# SCH.net
KiCad netlist of a schematic drawn in EasyEDA Pro
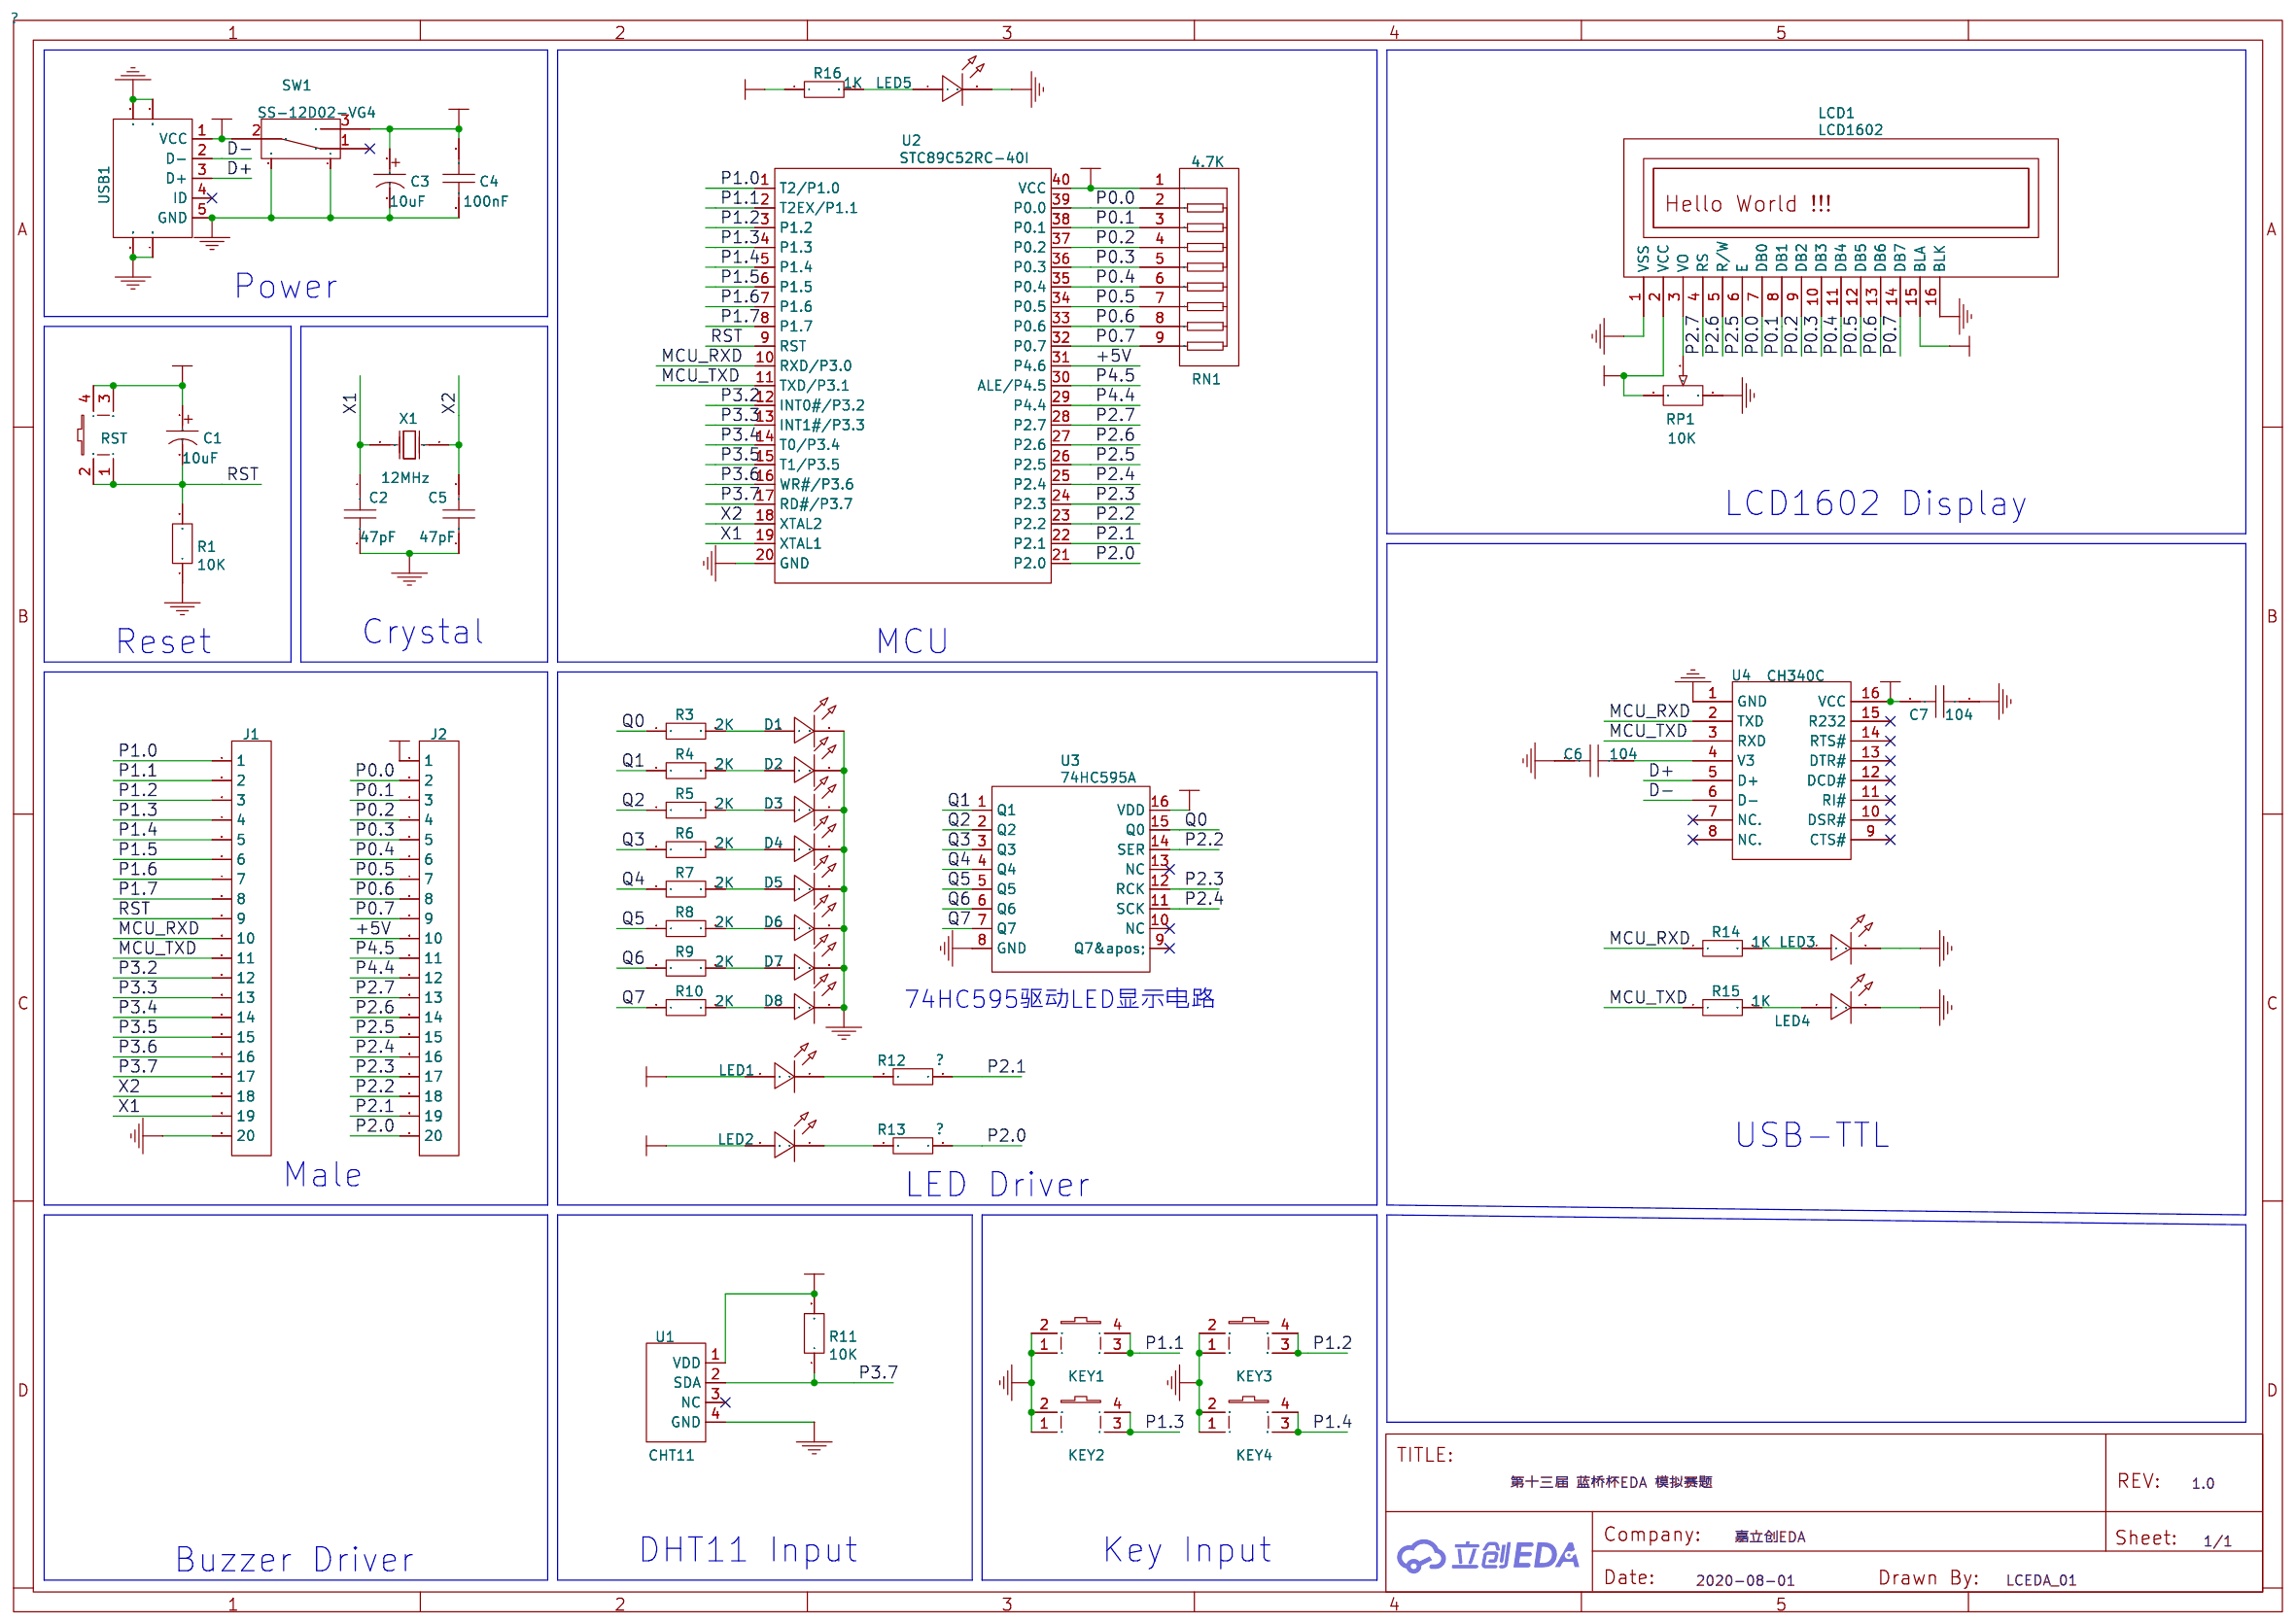
[diagram p0: schematic sheet]

(export (version "E")
  (design (tool "Eeschema 10.0.6"))
  (components
    (comp (ref "C1")
      (value "10uF")
      (fields (field (name "Manufacturer Part") "10uF 25V 5*11") (field (name "Manufacturer") "ValuePro"))
      (libsource (lib "easyedapro") (part "10uF"))
    )
    (comp (ref "C2")
      (value "47pF")
      (fields
        (field (name "Manufacturer Part") "CC81-N5S2L1B470KSE")
        (field (name "Manufacturer") "Guangdong Fenghua Advanced Tech")
      )
      (libsource (lib "easyedapro") (part "47pF"))
    )
    (comp (ref "C3")
      (value "10uF")
      (fields (field (name "Manufacturer Part") "10uF 25V 5*11") (field (name "Manufacturer") "ValuePro"))
      (libsource (lib "easyedapro") (part "10uF"))
    )
    (comp (ref "C4")
      (value "100nF")
      (fields
        (field (name "Manufacturer Part") "CC1H104ZA1FD3F5O10MF")
        (field (name "Manufacturer") "Dersonic")
      )
      (libsource (lib "easyedapro") (part "104"))
    )
    (comp (ref "C5")
      (value "47pF")
      (fields
        (field (name "Manufacturer Part") "CC81-N5S2L1B470KSE")
        (field (name "Manufacturer") "Guangdong Fenghua Advanced Tech")
      )
      (libsource (lib "easyedapro") (part "47pF"))
    )
    (comp (ref "C6")
      (value "104")
      (fields
        (field (name "Manufacturer Part") "CC1H104ZA1FD3F5O10MF")
        (field (name "Manufacturer") "Dersonic")
      )
      (libsource (lib "easyedapro") (part "104"))
    )
    (comp (ref "C7")
      (value "104")
      (fields
        (field (name "Manufacturer Part") "CC1H104ZA1FD3F5O10MF")
        (field (name "Manufacturer") "Dersonic")
      )
      (libsource (lib "easyedapro") (part "104"))
    )
    (comp (ref "D1")
      (value "LED-0805_B")
      (fields (field (name "Manufacturer Part") "D-B080508B1-KS2") (field (name "Manufacturer") "方舟 ARKLED"))
      (libsource (lib "easyedapro") (part "LED-0805_B"))
    )
    (comp (ref "D2")
      (value "LED-0805_B")
      (fields (field (name "Manufacturer Part") "D-B080508B1-KS2") (field (name "Manufacturer") "方舟 ARKLED"))
      (libsource (lib "easyedapro") (part "LED-0805_B"))
    )
    (comp (ref "D3")
      (value "LED-0805_B")
      (fields (field (name "Manufacturer Part") "D-B080508B1-KS2") (field (name "Manufacturer") "方舟 ARKLED"))
      (libsource (lib "easyedapro") (part "LED-0805_B"))
    )
    (comp (ref "D4")
      (value "LED-0805_B")
      (fields (field (name "Manufacturer Part") "D-B080508B1-KS2") (field (name "Manufacturer") "方舟 ARKLED"))
      (libsource (lib "easyedapro") (part "LED-0805_B"))
    )
    (comp (ref "D5")
      (value "LED-0805_B")
      (fields (field (name "Manufacturer Part") "D-B080508B1-KS2") (field (name "Manufacturer") "方舟 ARKLED"))
      (libsource (lib "easyedapro") (part "LED-0805_B"))
    )
    (comp (ref "D6")
      (value "LED-0805_B")
      (fields (field (name "Manufacturer Part") "D-B080508B1-KS2") (field (name "Manufacturer") "方舟 ARKLED"))
      (libsource (lib "easyedapro") (part "LED-0805_B"))
    )
    (comp (ref "D7")
      (value "LED-0805_B")
      (fields (field (name "Manufacturer Part") "D-B080508B1-KS2") (field (name "Manufacturer") "方舟 ARKLED"))
      (libsource (lib "easyedapro") (part "LED-0805_B"))
    )
    (comp (ref "D8")
      (value "LED-0805_B")
      (fields (field (name "Manufacturer Part") "D-B080508B1-KS2") (field (name "Manufacturer") "方舟 ARKLED"))
      (libsource (lib "easyedapro") (part "LED-0805_B"))
    )
    (comp (ref "J1") (value "HDR-M-2.54_1x20") (libsource (lib "easyedapro") (part "HDR-M-2.54_1x20")))
    (comp (ref "J2") (value "HDR-M-2.54_1x20") (libsource (lib "easyedapro") (part "HDR-M-2.54_1x20")))
    (comp (ref "KEY1")
      (value "K4-6×6_SMD")
      (fields (field (name "Manufacturer Part") "K2-6639SP-D4SC-04") (field (name "Manufacturer") "韩国韩荣"))
      (libsource (lib "easyedapro") (part "K4-6×6_SMD"))
    )
    (comp (ref "KEY2")
      (value "K4-6×6_SMD")
      (fields (field (name "Manufacturer Part") "K2-6639SP-D4SC-04") (field (name "Manufacturer") "韩国韩荣"))
      (libsource (lib "easyedapro") (part "K4-6×6_SMD"))
    )
    (comp (ref "KEY3")
      (value "K4-6×6_SMD")
      (fields (field (name "Manufacturer Part") "K2-6639SP-D4SC-04") (field (name "Manufacturer") "韩国韩荣"))
      (libsource (lib "easyedapro") (part "K4-6×6_SMD"))
    )
    (comp (ref "KEY4")
      (value "K4-6×6_SMD")
      (fields (field (name "Manufacturer Part") "K2-6639SP-D4SC-04") (field (name "Manufacturer") "韩国韩荣"))
      (libsource (lib "easyedapro") (part "K4-6×6_SMD"))
    )
    (comp (ref "LCD1")
      (value "LCD1602")
      (fields
        (field (name "Manufacturer Part") "LCM1602K-NSW-BBW")
        (field (name "Manufacturer") "LONTECH(厦门龙特)")
      )
      (libsource (lib "easyedapro") (part "LCD1602"))
    )
    (comp (ref "LED1")
      (value "LED-TH-3mm_B")
      (fields
        (field (name "Manufacturer Part") "204-10SUBC/S400-A4")
        (field (name "Manufacturer") "EVERLIGHT(台湾亿光)")
      )
      (libsource (lib "easyedapro") (part "LED-TH-3mm_B"))
    )
    (comp (ref "LED2")
      (value "LED-TH-3mm_G")
      (fields
        (field (name "Manufacturer Part") "204-10SYGD/S530-E3")
        (field (name "Manufacturer") "EVERLIGHT(台湾亿光)")
      )
      (libsource (lib "easyedapro") (part "LED-TH-3mm_G"))
    )
    (comp (ref "LED3")
      (value "LED-0805_B")
      (fields (field (name "Manufacturer Part") "D-B080508B1-KS2") (field (name "Manufacturer") "方舟 ARKLED"))
      (libsource (lib "easyedapro") (part "LED-0805_B"))
    )
    (comp (ref "LED4")
      (value "LED-0805_G")
      (fields (field (name "Manufacturer Part") "NCD0805G1") (field (name "Manufacturer") "国星光电"))
      (libsource (lib "easyedapro") (part "LED-0805_G"))
    )
    (comp (ref "LED5")
      (value "LED-TH-3mm_R")
      (fields
        (field (name "Manufacturer Part") "204-10SDRD/S530-A3-L")
        (field (name "Manufacturer") "EVERLIGHT(台湾亿光)")
      )
      (libsource (lib "easyedapro") (part "LED-TH-3mm_R"))
    )
    (comp (ref "R1")
      (value "10K")
      (fields (field (name "Manufacturer Part") "RN 1/4W 10K F T/B A1") (field (name "Manufacturer") "TyoHM"))
      (libsource (lib "easyedapro") (part "10K"))
    )
    (comp (ref "R3")
      (value "2K")
      (fields (field (name "Manufacturer Part") "ARG05FTC2001") (field (name "Manufacturer") "Viking Tech"))
      (libsource (lib "easyedapro") (part "2K"))
    )
    (comp (ref "R4")
      (value "2K")
      (fields (field (name "Manufacturer Part") "ARG05FTC2001") (field (name "Manufacturer") "Viking Tech"))
      (libsource (lib "easyedapro") (part "2K"))
    )
    (comp (ref "R5")
      (value "2K")
      (fields (field (name "Manufacturer Part") "ARG05FTC2001") (field (name "Manufacturer") "Viking Tech"))
      (libsource (lib "easyedapro") (part "2K"))
    )
    (comp (ref "R6")
      (value "2K")
      (fields (field (name "Manufacturer Part") "ARG05FTC2001") (field (name "Manufacturer") "Viking Tech"))
      (libsource (lib "easyedapro") (part "2K"))
    )
    (comp (ref "R7")
      (value "2K")
      (fields (field (name "Manufacturer Part") "ARG05FTC2001") (field (name "Manufacturer") "Viking Tech"))
      (libsource (lib "easyedapro") (part "2K"))
    )
    (comp (ref "R8")
      (value "2K")
      (fields (field (name "Manufacturer Part") "ARG05FTC2001") (field (name "Manufacturer") "Viking Tech"))
      (libsource (lib "easyedapro") (part "2K"))
    )
    (comp (ref "R9")
      (value "2K")
      (fields (field (name "Manufacturer Part") "ARG05FTC2001") (field (name "Manufacturer") "Viking Tech"))
      (libsource (lib "easyedapro") (part "2K"))
    )
    (comp (ref "R10")
      (value "2K")
      (fields (field (name "Manufacturer Part") "ARG05FTC2001") (field (name "Manufacturer") "Viking Tech"))
      (libsource (lib "easyedapro") (part "2K"))
    )
    (comp (ref "R11")
      (value "10K")
      (fields (field (name "Manufacturer Part") "RN 1/4W 10K F T/B A1") (field (name "Manufacturer") "TyoHM"))
      (libsource (lib "easyedapro") (part "10K"))
    )
    (comp (ref "R12")
      (value "？")
      (fields (field (name "Manufacturer Part") "RN1/2WS2KΩFT/BA1") (field (name "Manufacturer") "TyoHM"))
      (libsource (lib "easyedapro") (part "？"))
    )
    (comp (ref "R13")
      (value "？")
      (fields (field (name "Manufacturer Part") "RN1/2WS2KΩFT/BA1") (field (name "Manufacturer") "TyoHM"))
      (libsource (lib "easyedapro") (part "？"))
    )
    (comp (ref "R14")
      (value "1K")
      (fields (field (name "Manufacturer Part") "ARG05FTC2001") (field (name "Manufacturer") "Viking Tech"))
      (libsource (lib "easyedapro") (part "2K"))
    )
    (comp (ref "R15")
      (value "1K")
      (fields (field (name "Manufacturer Part") "ARG05FTC2001") (field (name "Manufacturer") "Viking Tech"))
      (libsource (lib "easyedapro") (part "2K"))
    )
    (comp (ref "R16")
      (value "1K")
      (fields (field (name "Manufacturer Part") "RN1/2WS2KΩFT/BA1") (field (name "Manufacturer") "TyoHM"))
      (libsource (lib "easyedapro") (part "？"))
    )
    (comp (ref "RN1")
      (value "4.7K")
      (fields (field (name "Manufacturer Part") "A09-472JP") (field (name "Manufacturer") "FH"))
      (libsource (lib "easyedapro") (part "4.7K"))
    )
    (comp (ref "RP1") (value "10K") (libsource (lib "") (part "10K_1")))
    (comp (ref "RST")
      (value "K4-6×6_SMD")
      (fields (field (name "Manufacturer Part") "K2-6639SP-D4SC-04") (field (name "Manufacturer") "韩国韩荣"))
      (libsource (lib "easyedapro") (part "K4-6×6_SMD"))
    )
    (comp (ref "SW1")
      (value "SS-12D02-VG4")
      (fields (field (name "Manufacturer") "Rectangular Connectors - Contacts"))
      (libsource (lib "easyedapro") (part "SS-12D02-VG4"))
    )
    (comp (ref "U1")
      (value "CHT11")
      (fields (field (name "Manufacturer") "CYBERSEN"))
      (libsource (lib "easyedapro") (part "CHT11"))
    )
    (comp (ref "U2")
      (value "STC89C52RC-40I")
      (fields (field (name "Manufacturer") "STC"))
      (libsource (lib "easyedapro") (part "STC89C52RC-40I"))
    )
    (comp (ref "U3")
      (value "74HC595A")
      (fields (field (name "Manufacturer") "FM"))
      (libsource (lib "easyedapro") (part "74HC595A"))
    )
    (comp (ref "U4")
      (value "CH340C")
      (fields (field (name "Manufacturer") "WCH"))
      (libsource (lib "easyedapro") (part "CH340C"))
    )
    (comp (ref "USB1")
      (value "USB-Micro_2")
      (fields (field (name "Manufacturer") "ValuePro"))
      (libsource (lib "easyedapro") (part "USB-Micro_2"))
    )
    (comp (ref "X1")
      (value "12MHz")
      (fields
        (field (name "Manufacturer Part") "B12000J233")
        (field (name "Manufacturer") "ZheJiang East Crystal Elec")
      )
      (libsource (lib "easyedapro") (part "12MHz"))
    )
  )
  (nets
    (net (code "1") (name "+5V") (class "Default")
      (node (ref "C1") (pin "1") (pinfunction "1_1") (pintype "input"))
      (node (ref "C3") (pin "1") (pinfunction "1_1") (pintype "input"))
      (node (ref "C4") (pin "2") (pinfunction "2_2") (pintype "unspecified"))
      (node (ref "J2") (pin "1") (pinfunction "1_1") (pintype "unspecified"))
      (node (ref "J2") (pin "10") (pinfunction "10_10") (pintype "unspecified"))
      (node (ref "LCD1") (pin "15") (pinfunction "BLA_15") (pintype "unspecified"))
      (node (ref "LCD1") (pin "2") (pinfunction "VCC_2") (pintype "unspecified"))
      (node (ref "LED1") (pin "1") (pinfunction "1_1") (pintype "unspecified"))
      (node (ref "LED2") (pin "1") (pinfunction "1_1") (pintype "unspecified"))
      (node (ref "R11") (pin "2") (pinfunction "2_2") (pintype "unspecified"))
      (node (ref "R16") (pin "1") (pinfunction "1_1") (pintype "unspecified"))
      (node (ref "RN1") (pin "1") (pinfunction "1_1") (pintype "unspecified"))
      (node (ref "RP1") (pin "1") (pinfunction "1_1") (pintype "input"))
      (node (ref "RST") (pin "3") (pinfunction "3_3") (pintype "unspecified"))
      (node (ref "RST") (pin "4") (pinfunction "4_4") (pintype "unspecified"))
      (node (ref "SW1") (pin "3") (pinfunction "3_3") (pintype "unspecified"))
      (node (ref "U1") (pin "1") (pinfunction "VDD_1") (pintype "unspecified"))
      (node (ref "U2") (pin "31") (pinfunction "P4.6_31") (pintype "unspecified"))
      (node (ref "U2") (pin "40") (pinfunction "VCC_40") (pintype "unspecified"))
      (node (ref "U3") (pin "16") (pinfunction "VDD_16") (pintype "unspecified"))
    )
    (net (code "2") (name "/D+") (class "Default")
      (node (ref "U4") (pin "5") (pinfunction "D+_5") (pintype "unspecified"))
      (node (ref "USB1") (pin "3") (pinfunction "D+_3") (pintype "input"))
    )
    (net (code "3") (name "/D-") (class "Default")
      (node (ref "U4") (pin "6") (pinfunction "D-_6") (pintype "unspecified"))
      (node (ref "USB1") (pin "2") (pinfunction "D-_2") (pintype "input"))
    )
    (net (code "4") (name "/MCU_RXD") (class "Default")
      (node (ref "J1") (pin "10") (pinfunction "10_10") (pintype "unspecified"))
      (node (ref "R14") (pin "1") (pinfunction "1_1") (pintype "unspecified"))
      (node (ref "U2") (pin "10") (pinfunction "RXD/P3.0_10") (pintype "unspecified"))
      (node (ref "U4") (pin "2") (pinfunction "TXD_2") (pintype "unspecified"))
    )
    (net (code "5") (name "/MCU_TXD") (class "Default")
      (node (ref "J1") (pin "11") (pinfunction "11_11") (pintype "unspecified"))
      (node (ref "R15") (pin "1") (pinfunction "1_1") (pintype "unspecified"))
      (node (ref "U2") (pin "11") (pinfunction "TXD/P3.1_11") (pintype "unspecified"))
      (node (ref "U4") (pin "3") (pinfunction "RXD_3") (pintype "unspecified"))
    )
    (net (code "6") (name "/P0.0") (class "Default")
      (node (ref "J2") (pin "2") (pinfunction "2_2") (pintype "unspecified"))
      (node (ref "LCD1") (pin "7") (pinfunction "DB0_7") (pintype "unspecified"))
      (node (ref "RN1") (pin "2") (pinfunction "2_2") (pintype "unspecified"))
      (node (ref "U2") (pin "39") (pinfunction "P0.0_39") (pintype "unspecified"))
    )
    (net (code "7") (name "/P0.1") (class "Default")
      (node (ref "J2") (pin "3") (pinfunction "3_3") (pintype "unspecified"))
      (node (ref "LCD1") (pin "8") (pinfunction "DB1_8") (pintype "unspecified"))
      (node (ref "RN1") (pin "3") (pinfunction "3_3") (pintype "unspecified"))
      (node (ref "U2") (pin "38") (pinfunction "P0.1_38") (pintype "unspecified"))
    )
    (net (code "8") (name "/P0.2") (class "Default")
      (node (ref "J2") (pin "4") (pinfunction "4_4") (pintype "unspecified"))
      (node (ref "LCD1") (pin "9") (pinfunction "DB2_9") (pintype "unspecified"))
      (node (ref "RN1") (pin "4") (pinfunction "4_4") (pintype "unspecified"))
      (node (ref "U2") (pin "37") (pinfunction "P0.2_37") (pintype "unspecified"))
    )
    (net (code "9") (name "/P0.3") (class "Default")
      (node (ref "J2") (pin "5") (pinfunction "5_5") (pintype "unspecified"))
      (node (ref "LCD1") (pin "10") (pinfunction "DB3_10") (pintype "unspecified"))
      (node (ref "RN1") (pin "5") (pinfunction "5_5") (pintype "unspecified"))
      (node (ref "U2") (pin "36") (pinfunction "P0.3_36") (pintype "unspecified"))
    )
    (net (code "10") (name "/P0.4") (class "Default")
      (node (ref "J2") (pin "6") (pinfunction "6_6") (pintype "unspecified"))
      (node (ref "LCD1") (pin "11") (pinfunction "DB4_11") (pintype "unspecified"))
      (node (ref "RN1") (pin "6") (pinfunction "6_6") (pintype "unspecified"))
      (node (ref "U2") (pin "35") (pinfunction "P0.4_35") (pintype "unspecified"))
    )
    (net (code "11") (name "/P0.5") (class "Default")
      (node (ref "J2") (pin "7") (pinfunction "7_7") (pintype "unspecified"))
      (node (ref "LCD1") (pin "12") (pinfunction "DB5_12") (pintype "unspecified"))
      (node (ref "RN1") (pin "7") (pinfunction "7_7") (pintype "unspecified"))
      (node (ref "U2") (pin "34") (pinfunction "P0.5_34") (pintype "unspecified"))
    )
    (net (code "12") (name "/P0.6") (class "Default")
      (node (ref "J2") (pin "8") (pinfunction "8_8") (pintype "unspecified"))
      (node (ref "LCD1") (pin "13") (pinfunction "DB6_13") (pintype "unspecified"))
      (node (ref "RN1") (pin "8") (pinfunction "8_8") (pintype "unspecified"))
      (node (ref "U2") (pin "33") (pinfunction "P0.6_33") (pintype "unspecified"))
    )
    (net (code "13") (name "/P0.7") (class "Default")
      (node (ref "J2") (pin "9") (pinfunction "9_9") (pintype "unspecified"))
      (node (ref "LCD1") (pin "14") (pinfunction "DB7_14") (pintype "unspecified"))
      (node (ref "RN1") (pin "9") (pinfunction "9_9") (pintype "unspecified"))
      (node (ref "U2") (pin "32") (pinfunction "P0.7_32") (pintype "unspecified"))
    )
    (net (code "14") (name "/P1.0") (class "Default")
      (node (ref "J1") (pin "1") (pinfunction "1_1") (pintype "unspecified"))
      (node (ref "U2") (pin "1") (pinfunction "T2/P1.0_1") (pintype "unspecified"))
    )
    (net (code "15") (name "/P1.1") (class "Default")
      (node (ref "J1") (pin "2") (pinfunction "2_2") (pintype "unspecified"))
      (node (ref "KEY1") (pin "3") (pinfunction "3_3") (pintype "unspecified"))
      (node (ref "KEY1") (pin "4") (pinfunction "4_4") (pintype "unspecified"))
      (node (ref "U2") (pin "2") (pinfunction "T2EX/P1.1_2") (pintype "unspecified"))
    )
    (net (code "16") (name "/P1.2") (class "Default")
      (node (ref "J1") (pin "3") (pinfunction "3_3") (pintype "unspecified"))
      (node (ref "KEY3") (pin "3") (pinfunction "3_3") (pintype "unspecified"))
      (node (ref "KEY3") (pin "4") (pinfunction "4_4") (pintype "unspecified"))
      (node (ref "U2") (pin "3") (pinfunction "P1.2_3") (pintype "unspecified"))
    )
    (net (code "17") (name "/P1.3") (class "Default")
      (node (ref "J1") (pin "4") (pinfunction "4_4") (pintype "unspecified"))
      (node (ref "KEY2") (pin "3") (pinfunction "3_3") (pintype "unspecified"))
      (node (ref "KEY2") (pin "4") (pinfunction "4_4") (pintype "unspecified"))
      (node (ref "U2") (pin "4") (pinfunction "P1.3_4") (pintype "unspecified"))
    )
    (net (code "18") (name "/P1.4") (class "Default")
      (node (ref "J1") (pin "5") (pinfunction "5_5") (pintype "unspecified"))
      (node (ref "KEY4") (pin "3") (pinfunction "3_3") (pintype "unspecified"))
      (node (ref "KEY4") (pin "4") (pinfunction "4_4") (pintype "unspecified"))
      (node (ref "U2") (pin "5") (pinfunction "P1.4_5") (pintype "unspecified"))
    )
    (net (code "19") (name "/P1.5") (class "Default")
      (node (ref "J1") (pin "6") (pinfunction "6_6") (pintype "unspecified"))
      (node (ref "U2") (pin "6") (pinfunction "P1.5_6") (pintype "unspecified"))
    )
    (net (code "20") (name "/P1.6") (class "Default")
      (node (ref "J1") (pin "7") (pinfunction "7_7") (pintype "unspecified"))
      (node (ref "U2") (pin "7") (pinfunction "P1.6_7") (pintype "unspecified"))
    )
    (net (code "21") (name "/P1.7") (class "Default")
      (node (ref "J1") (pin "8") (pinfunction "8_8") (pintype "unspecified"))
      (node (ref "U2") (pin "8") (pinfunction "P1.7_8") (pintype "unspecified"))
    )
    (net (code "22") (name "/P2.0") (class "Default")
      (node (ref "J2") (pin "20") (pinfunction "20_20") (pintype "unspecified"))
      (node (ref "R13") (pin "2") (pinfunction "2_2") (pintype "unspecified"))
      (node (ref "U2") (pin "21") (pinfunction "P2.0_21") (pintype "unspecified"))
    )
    (net (code "23") (name "/P2.1") (class "Default")
      (node (ref "J2") (pin "19") (pinfunction "19_19") (pintype "unspecified"))
      (node (ref "R12") (pin "2") (pinfunction "2_2") (pintype "unspecified"))
      (node (ref "U2") (pin "22") (pinfunction "P2.1_22") (pintype "unspecified"))
    )
    (net (code "24") (name "/P2.2") (class "Default")
      (node (ref "J2") (pin "18") (pinfunction "18_18") (pintype "unspecified"))
      (node (ref "U2") (pin "23") (pinfunction "P2.2_23") (pintype "unspecified"))
      (node (ref "U3") (pin "14") (pinfunction "SER_14") (pintype "unspecified"))
    )
    (net (code "25") (name "/P2.3") (class "Default")
      (node (ref "J2") (pin "17") (pinfunction "17_17") (pintype "unspecified"))
      (node (ref "U2") (pin "24") (pinfunction "P2.3_24") (pintype "unspecified"))
      (node (ref "U3") (pin "12") (pinfunction "RCK_12") (pintype "unspecified"))
    )
    (net (code "26") (name "/P2.4") (class "Default")
      (node (ref "J2") (pin "16") (pinfunction "16_16") (pintype "unspecified"))
      (node (ref "U2") (pin "25") (pinfunction "P2.4_25") (pintype "unspecified"))
      (node (ref "U3") (pin "11") (pinfunction "SCK_11") (pintype "unspecified"))
    )
    (net (code "27") (name "/P2.5") (class "Default")
      (node (ref "J2") (pin "15") (pinfunction "15_15") (pintype "unspecified"))
      (node (ref "LCD1") (pin "6") (pinfunction "E_6") (pintype "unspecified"))
      (node (ref "U2") (pin "26") (pinfunction "P2.5_26") (pintype "unspecified"))
    )
    (net (code "28") (name "/P2.6") (class "Default")
      (node (ref "J2") (pin "14") (pinfunction "14_14") (pintype "unspecified"))
      (node (ref "LCD1") (pin "5") (pinfunction "R/W_5") (pintype "unspecified"))
      (node (ref "U2") (pin "27") (pinfunction "P2.6_27") (pintype "unspecified"))
    )
    (net (code "29") (name "/P2.7") (class "Default")
      (node (ref "J2") (pin "13") (pinfunction "13_13") (pintype "unspecified"))
      (node (ref "LCD1") (pin "4") (pinfunction "RS_4") (pintype "unspecified"))
      (node (ref "U2") (pin "28") (pinfunction "P2.7_28") (pintype "unspecified"))
    )
    (net (code "30") (name "/P3.2") (class "Default")
      (node (ref "J1") (pin "12") (pinfunction "12_12") (pintype "unspecified"))
      (node (ref "U2") (pin "12") (pinfunction "INT0#/P3.2_12") (pintype "unspecified"))
    )
    (net (code "31") (name "/P3.3") (class "Default")
      (node (ref "J1") (pin "13") (pinfunction "13_13") (pintype "unspecified"))
      (node (ref "U2") (pin "13") (pinfunction "INT1#/P3.3_13") (pintype "unspecified"))
    )
    (net (code "32") (name "/P3.4") (class "Default")
      (node (ref "J1") (pin "14") (pinfunction "14_14") (pintype "unspecified"))
      (node (ref "U2") (pin "14") (pinfunction "T0/P3.4_14") (pintype "unspecified"))
    )
    (net (code "33") (name "/P3.5") (class "Default")
      (node (ref "J1") (pin "15") (pinfunction "15_15") (pintype "unspecified"))
      (node (ref "U2") (pin "15") (pinfunction "T1/P3.5_15") (pintype "unspecified"))
    )
    (net (code "34") (name "/P3.6") (class "Default")
      (node (ref "J1") (pin "16") (pinfunction "16_16") (pintype "unspecified"))
      (node (ref "U2") (pin "16") (pinfunction "WR#/P3.6_16") (pintype "unspecified"))
    )
    (net (code "35") (name "/P3.7") (class "Default")
      (node (ref "J1") (pin "17") (pinfunction "17_17") (pintype "unspecified"))
      (node (ref "R11") (pin "1") (pinfunction "1_1") (pintype "unspecified"))
      (node (ref "U1") (pin "2") (pinfunction "SDA_2") (pintype "unspecified"))
      (node (ref "U2") (pin "17") (pinfunction "RD#/P3.7_17") (pintype "unspecified"))
    )
    (net (code "36") (name "/P4.4") (class "Default")
      (node (ref "J2") (pin "12") (pinfunction "12_12") (pintype "unspecified"))
      (node (ref "U2") (pin "29") (pinfunction "P4.4_29") (pintype "unspecified"))
    )
    (net (code "37") (name "/P4.5") (class "Default")
      (node (ref "J2") (pin "11") (pinfunction "11_11") (pintype "unspecified"))
      (node (ref "U2") (pin "30") (pinfunction "ALE/P4.5_30") (pintype "unspecified"))
    )
    (net (code "38") (name "/Q0") (class "Default")
      (node (ref "R3") (pin "1") (pinfunction "1_1") (pintype "unspecified"))
      (node (ref "U3") (pin "15") (pinfunction "Q0_15") (pintype "unspecified"))
    )
    (net (code "39") (name "/Q1") (class "Default")
      (node (ref "R4") (pin "1") (pinfunction "1_1") (pintype "unspecified"))
      (node (ref "U3") (pin "1") (pinfunction "Q1_1") (pintype "unspecified"))
    )
    (net (code "40") (name "/Q2") (class "Default")
      (node (ref "R5") (pin "1") (pinfunction "1_1") (pintype "unspecified"))
      (node (ref "U3") (pin "2") (pinfunction "Q2_2") (pintype "unspecified"))
    )
    (net (code "41") (name "/Q3") (class "Default")
      (node (ref "R6") (pin "1") (pinfunction "1_1") (pintype "unspecified"))
      (node (ref "U3") (pin "3") (pinfunction "Q3_3") (pintype "unspecified"))
    )
    (net (code "42") (name "/Q4") (class "Default")
      (node (ref "R7") (pin "1") (pinfunction "1_1") (pintype "unspecified"))
      (node (ref "U3") (pin "4") (pinfunction "Q4_4") (pintype "unspecified"))
    )
    (net (code "43") (name "/Q5") (class "Default")
      (node (ref "R8") (pin "1") (pinfunction "1_1") (pintype "unspecified"))
      (node (ref "U3") (pin "5") (pinfunction "Q5_5") (pintype "unspecified"))
    )
    (net (code "44") (name "/Q6") (class "Default")
      (node (ref "R9") (pin "1") (pinfunction "1_1") (pintype "unspecified"))
      (node (ref "U3") (pin "6") (pinfunction "Q6_6") (pintype "unspecified"))
    )
    (net (code "45") (name "/Q7") (class "Default")
      (node (ref "R10") (pin "1") (pinfunction "1_1") (pintype "unspecified"))
      (node (ref "U3") (pin "7") (pinfunction "Q7_7") (pintype "unspecified"))
    )
    (net (code "46") (name "/RST") (class "Default")
      (node (ref "C1") (pin "2") (pinfunction "2_2") (pintype "input"))
      (node (ref "J1") (pin "9") (pinfunction "9_9") (pintype "unspecified"))
      (node (ref "R1") (pin "2") (pinfunction "2_2") (pintype "unspecified"))
      (node (ref "RST") (pin "1") (pinfunction "1_1") (pintype "unspecified"))
      (node (ref "RST") (pin "2") (pinfunction "2_2") (pintype "unspecified"))
      (node (ref "U2") (pin "9") (pinfunction "RST_9") (pintype "unspecified"))
    )
    (net (code "47") (name "/X1") (class "Default")
      (node (ref "C2") (pin "1") (pinfunction "1_1") (pintype "unspecified"))
      (node (ref "J1") (pin "19") (pinfunction "19_19") (pintype "unspecified"))
      (node (ref "U2") (pin "19") (pinfunction "XTAL1_19") (pintype "unspecified"))
      (node (ref "X1") (pin "2") (pinfunction "OSC2_2") (pintype "input"))
    )
    (net (code "48") (name "/X2") (class "Default")
      (node (ref "C5") (pin "2") (pinfunction "2_2") (pintype "unspecified"))
      (node (ref "J1") (pin "18") (pinfunction "18_18") (pintype "unspecified"))
      (node (ref "U2") (pin "18") (pinfunction "XTAL2_18") (pintype "unspecified"))
      (node (ref "X1") (pin "1") (pinfunction "OSC1_1") (pintype "input"))
    )
    (net (code "49") (name "GND") (class "Default")
      (node (ref "C2") (pin "2") (pinfunction "2_2") (pintype "unspecified"))
      (node (ref "C3") (pin "2") (pinfunction "2_2") (pintype "input"))
      (node (ref "C4") (pin "1") (pinfunction "1_1") (pintype "unspecified"))
      (node (ref "C5") (pin "1") (pinfunction "1_1") (pintype "unspecified"))
      (node (ref "C6") (pin "2") (pinfunction "2_2") (pintype "unspecified"))
      (node (ref "C7") (pin "1") (pinfunction "1_1") (pintype "unspecified"))
      (node (ref "D1") (pin "2") (pinfunction "2_2") (pintype "unspecified"))
      (node (ref "D2") (pin "2") (pinfunction "2_2") (pintype "unspecified"))
      (node (ref "D3") (pin "2") (pinfunction "2_2") (pintype "unspecified"))
      (node (ref "D4") (pin "2") (pinfunction "2_2") (pintype "unspecified"))
      (node (ref "D5") (pin "2") (pinfunction "2_2") (pintype "unspecified"))
      (node (ref "D6") (pin "2") (pinfunction "2_2") (pintype "unspecified"))
      (node (ref "D7") (pin "2") (pinfunction "2_2") (pintype "unspecified"))
      (node (ref "D8") (pin "2") (pinfunction "2_2") (pintype "unspecified"))
      (node (ref "J1") (pin "20") (pinfunction "20_20") (pintype "unspecified"))
      (node (ref "KEY1") (pin "1") (pinfunction "1_1") (pintype "unspecified"))
      (node (ref "KEY1") (pin "2") (pinfunction "2_2") (pintype "unspecified"))
      (node (ref "KEY2") (pin "1") (pinfunction "1_1") (pintype "unspecified"))
      (node (ref "KEY2") (pin "2") (pinfunction "2_2") (pintype "unspecified"))
      (node (ref "KEY3") (pin "1") (pinfunction "1_1") (pintype "unspecified"))
      (node (ref "KEY3") (pin "2") (pinfunction "2_2") (pintype "unspecified"))
      (node (ref "KEY4") (pin "1") (pinfunction "1_1") (pintype "unspecified"))
      (node (ref "KEY4") (pin "2") (pinfunction "2_2") (pintype "unspecified"))
      (node (ref "LCD1") (pin "1") (pinfunction "VSS_1") (pintype "unspecified"))
      (node (ref "LCD1") (pin "16") (pinfunction "BLK_16") (pintype "unspecified"))
      (node (ref "LED3") (pin "2") (pinfunction "2_2") (pintype "unspecified"))
      (node (ref "LED4") (pin "2") (pinfunction "2_2") (pintype "unspecified"))
      (node (ref "LED5") (pin "2") (pinfunction "2_2") (pintype "unspecified"))
      (node (ref "R1") (pin "1") (pinfunction "1_1") (pintype "unspecified"))
      (node (ref "RP1") (pin "3") (pinfunction "3_3") (pintype "input"))
      (node (ref "SW1") (pin "4") (pinfunction "4_4") (pintype "unspecified"))
      (node (ref "SW1") (pin "5") (pinfunction "5_5") (pintype "unspecified"))
      (node (ref "U1") (pin "4") (pinfunction "GND_4") (pintype "unspecified"))
      (node (ref "U2") (pin "20") (pinfunction "GND_20") (pintype "unspecified"))
      (node (ref "U3") (pin "8") (pinfunction "GND_8") (pintype "unspecified"))
      (node (ref "U4") (pin "1") (pinfunction "GND_1") (pintype "unspecified"))
      (node (ref "USB1") (pin "5") (pinfunction "GND_5") (pintype "input"))
      (node (ref "USB1") (pin "6") (pinfunction "SH3_6") (pintype "unspecified"))
      (node (ref "USB1") (pin "7") (pinfunction "SH4_7") (pintype "unspecified"))
      (node (ref "USB1") (pin "8") (pinfunction "SH1_8") (pintype "unspecified"))
      (node (ref "USB1") (pin "9") (pinfunction "SH2_9") (pintype "unspecified"))
    )
    (net (code "50") (name "Net-(D1-Pad1)") (class "Default")
      (node (ref "D1") (pin "1") (pinfunction "1_1") (pintype "unspecified"))
      (node (ref "R3") (pin "2") (pinfunction "2_2") (pintype "unspecified"))
    )
    (net (code "51") (name "Net-(D2-Pad1)") (class "Default")
      (node (ref "D2") (pin "1") (pinfunction "1_1") (pintype "unspecified"))
      (node (ref "R4") (pin "2") (pinfunction "2_2") (pintype "unspecified"))
    )
    (net (code "52") (name "Net-(D3-Pad1)") (class "Default")
      (node (ref "D3") (pin "1") (pinfunction "1_1") (pintype "unspecified"))
      (node (ref "R5") (pin "2") (pinfunction "2_2") (pintype "unspecified"))
    )
    (net (code "53") (name "Net-(D4-Pad1)") (class "Default")
      (node (ref "D4") (pin "1") (pinfunction "1_1") (pintype "unspecified"))
      (node (ref "R6") (pin "2") (pinfunction "2_2") (pintype "unspecified"))
    )
    (net (code "54") (name "Net-(D5-Pad1)") (class "Default")
      (node (ref "D5") (pin "1") (pinfunction "1_1") (pintype "unspecified"))
      (node (ref "R7") (pin "2") (pinfunction "2_2") (pintype "unspecified"))
    )
    (net (code "55") (name "Net-(D6-Pad1)") (class "Default")
      (node (ref "D6") (pin "1") (pinfunction "1_1") (pintype "unspecified"))
      (node (ref "R8") (pin "2") (pinfunction "2_2") (pintype "unspecified"))
    )
    (net (code "56") (name "Net-(D7-Pad1)") (class "Default")
      (node (ref "D7") (pin "1") (pinfunction "1_1") (pintype "unspecified"))
      (node (ref "R9") (pin "2") (pinfunction "2_2") (pintype "unspecified"))
    )
    (net (code "57") (name "Net-(D8-Pad1)") (class "Default")
      (node (ref "D8") (pin "1") (pinfunction "1_1") (pintype "unspecified"))
      (node (ref "R10") (pin "2") (pinfunction "2_2") (pintype "unspecified"))
    )
    (net (code "58") (name "Net-(LCD1-VO)") (class "Default")
      (node (ref "LCD1") (pin "3") (pinfunction "VO_3") (pintype "unspecified"))
      (node (ref "RP1") (pin "2") (pinfunction "2_2") (pintype "input"))
    )
    (net (code "59") (name "Net-(LED1-Pad2)") (class "Default")
      (node (ref "LED1") (pin "2") (pinfunction "2_2") (pintype "unspecified"))
      (node (ref "R12") (pin "1") (pinfunction "1_1") (pintype "unspecified"))
    )
    (net (code "60") (name "Net-(LED2-Pad2)") (class "Default")
      (node (ref "LED2") (pin "2") (pinfunction "2_2") (pintype "unspecified"))
      (node (ref "R13") (pin "1") (pinfunction "1_1") (pintype "unspecified"))
    )
    (net (code "61") (name "Net-(LED3-Pad1)") (class "Default")
      (node (ref "LED3") (pin "1") (pinfunction "1_1") (pintype "unspecified"))
      (node (ref "R14") (pin "2") (pinfunction "2_2") (pintype "unspecified"))
    )
    (net (code "62") (name "Net-(LED4-Pad1)") (class "Default")
      (node (ref "LED4") (pin "1") (pinfunction "1_1") (pintype "unspecified"))
      (node (ref "R15") (pin "2") (pinfunction "2_2") (pintype "unspecified"))
    )
    (net (code "63") (name "Net-(LED5-Pad1)") (class "Default")
      (node (ref "LED5") (pin "1") (pinfunction "1_1") (pintype "unspecified"))
      (node (ref "R16") (pin "2") (pinfunction "2_2") (pintype "unspecified"))
    )
    (net (code "64") (name "Net-(U4-V3)") (class "Default")
      (node (ref "C6") (pin "1") (pinfunction "1_1") (pintype "unspecified"))
      (node (ref "U4") (pin "4") (pinfunction "V3_4") (pintype "unspecified"))
    )
    (net (code "65") (name "VCC") (class "Default")
      (node (ref "C7") (pin "2") (pinfunction "2_2") (pintype "unspecified"))
      (node (ref "SW1") (pin "2") (pinfunction "2_2") (pintype "unspecified"))
      (node (ref "U4") (pin "16") (pinfunction "VCC_16") (pintype "unspecified"))
      (node (ref "USB1") (pin "1") (pinfunction "VCC_1") (pintype "input"))
    )
    (net (code "66") (name "unconnected-(SW1-Pad1)") (class "Default")
      (node (ref "SW1") (pin "1") (pinfunction "1_1") (pintype "unspecified+no_connect"))
    )
    (net (code "67") (name "unconnected-(U1-NC-Pad3)") (class "Default")
      (node (ref "U1") (pin "3") (pinfunction "NC_3") (pintype "unspecified+no_connect"))
    )
    (net (code "68") (name "unconnected-(U3-NC-Pad10)") (class "Default")
      (node (ref "U3") (pin "10") (pinfunction "NC_10") (pintype "unspecified+no_connect"))
    )
    (net (code "69") (name "unconnected-(U3-NC-Pad13)") (class "Default")
      (node (ref "U3") (pin "13") (pinfunction "NC_13") (pintype "unspecified+no_connect"))
    )
    (net (code "70") (name "unconnected-(U3-Q7&apos;-Pad9)") (class "Default")
      (node (ref "U3") (pin "9") (pinfunction "Q7&apos;_9") (pintype "unspecified+no_connect"))
    )
    (net (code "71") (name "unconnected-(U4-CTS#-Pad9)") (class "Default")
      (node (ref "U4") (pin "9") (pinfunction "CTS#_9") (pintype "unspecified+no_connect"))
    )
    (net (code "72") (name "unconnected-(U4-DCD#-Pad12)") (class "Default")
      (node (ref "U4") (pin "12") (pinfunction "DCD#_12") (pintype "unspecified+no_connect"))
    )
    (net (code "73") (name "unconnected-(U4-DSR#-Pad10)") (class "Default")
      (node (ref "U4") (pin "10") (pinfunction "DSR#_10") (pintype "unspecified+no_connect"))
    )
    (net (code "74") (name "unconnected-(U4-DTR#-Pad13)") (class "Default")
      (node (ref "U4") (pin "13") (pinfunction "DTR#_13") (pintype "unspecified+no_connect"))
    )
    (net (code "75") (name "unconnected-(U4-NC.-Pad7)") (class "Default")
      (node (ref "U4") (pin "7") (pinfunction "NC._7") (pintype "unspecified+no_connect"))
    )
    (net (code "76") (name "unconnected-(U4-NC.-Pad8)") (class "Default")
      (node (ref "U4") (pin "8") (pinfunction "NC._8") (pintype "unspecified+no_connect"))
    )
    (net (code "77") (name "unconnected-(U4-R232-Pad15)") (class "Default")
      (node (ref "U4") (pin "15") (pinfunction "R232_15") (pintype "unspecified+no_connect"))
    )
    (net (code "78") (name "unconnected-(U4-RI#-Pad11)") (class "Default")
      (node (ref "U4") (pin "11") (pinfunction "RI#_11") (pintype "unspecified+no_connect"))
    )
    (net (code "79") (name "unconnected-(U4-RTS#-Pad14)") (class "Default")
      (node (ref "U4") (pin "14") (pinfunction "RTS#_14") (pintype "unspecified+no_connect"))
    )
    (net (code "80") (name "unconnected-(USB1-ID-Pad4)") (class "Default")
      (node (ref "USB1") (pin "4") (pinfunction "ID_4") (pintype "input+no_connect"))
    )
  )
)
